# Top_Level.net
KiCad netlist of a schematic drawn in Altium Designer
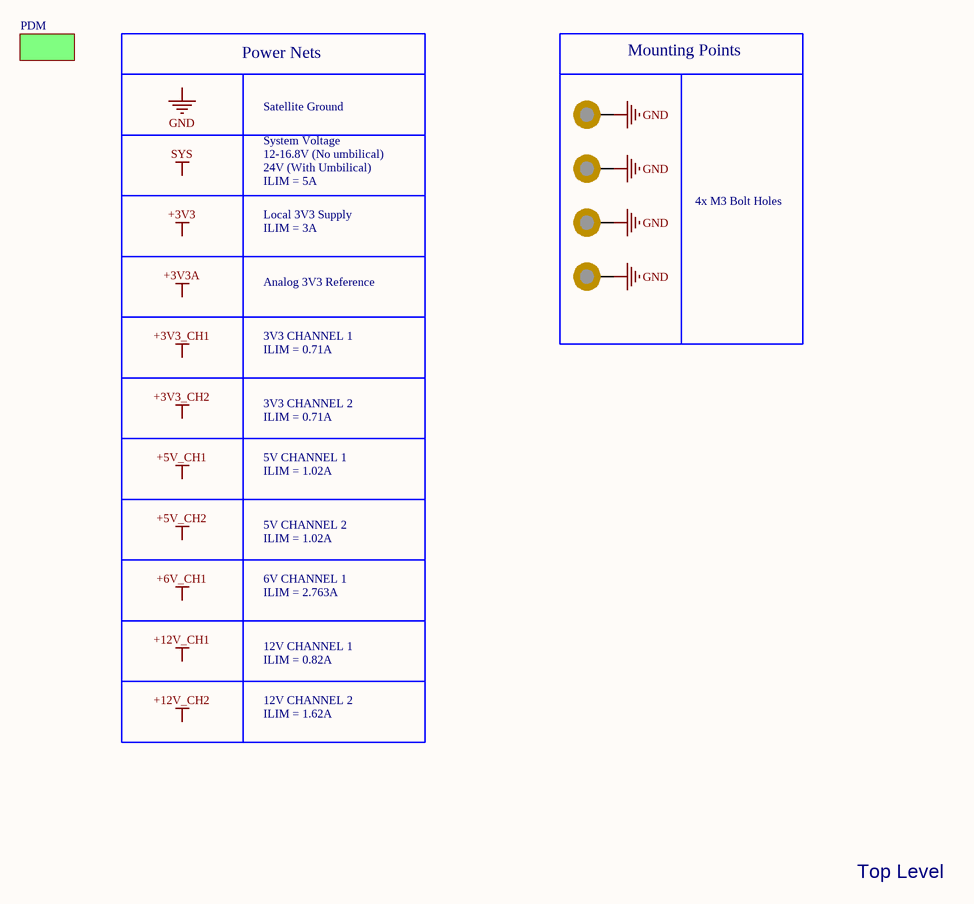
[diagram p0: Top_Level.SchDoc]

(export (version "E")
  (design (tool "Eeschema 10.0.6"))
  (components
    (comp (ref "MECH1")
      (value "M3 Mounting Hole")
      (footprint "M3 Mounting Hole")
      (libsource (lib "Ahristi_Library") (part "M3 Mounting Hole"))
    )
    (comp (ref "MECH2")
      (value "M3 Mounting Hole")
      (footprint "M3 Mounting Hole")
      (libsource (lib "Ahristi_Library") (part "M3 Mounting Hole"))
    )
    (comp (ref "MECH3")
      (value "M3 Mounting Hole")
      (footprint "M3 Mounting Hole")
      (libsource (lib "Ahristi_Library") (part "M3 Mounting Hole"))
    )
    (comp (ref "MECH4")
      (value "M3 Mounting Hole")
      (footprint "M3 Mounting Hole")
      (libsource (lib "Ahristi_Library") (part "M3 Mounting Hole"))
    )
  )
  (nets
    (net (code "10") (name "GND") (class "Default")
      (node (ref "MECH1") (pin "1") (pinfunction "1_1") (pintype "passive"))
      (node (ref "MECH2") (pin "1") (pinfunction "1_1") (pintype "passive"))
      (node (ref "MECH3") (pin "1") (pinfunction "1_1") (pintype "passive"))
      (node (ref "MECH4") (pin "1") (pinfunction "1_1") (pintype "passive"))
    )
  )
)
